# MAIN_Schematic.net
KiCad netlist of a schematic drawn in Altium Designer
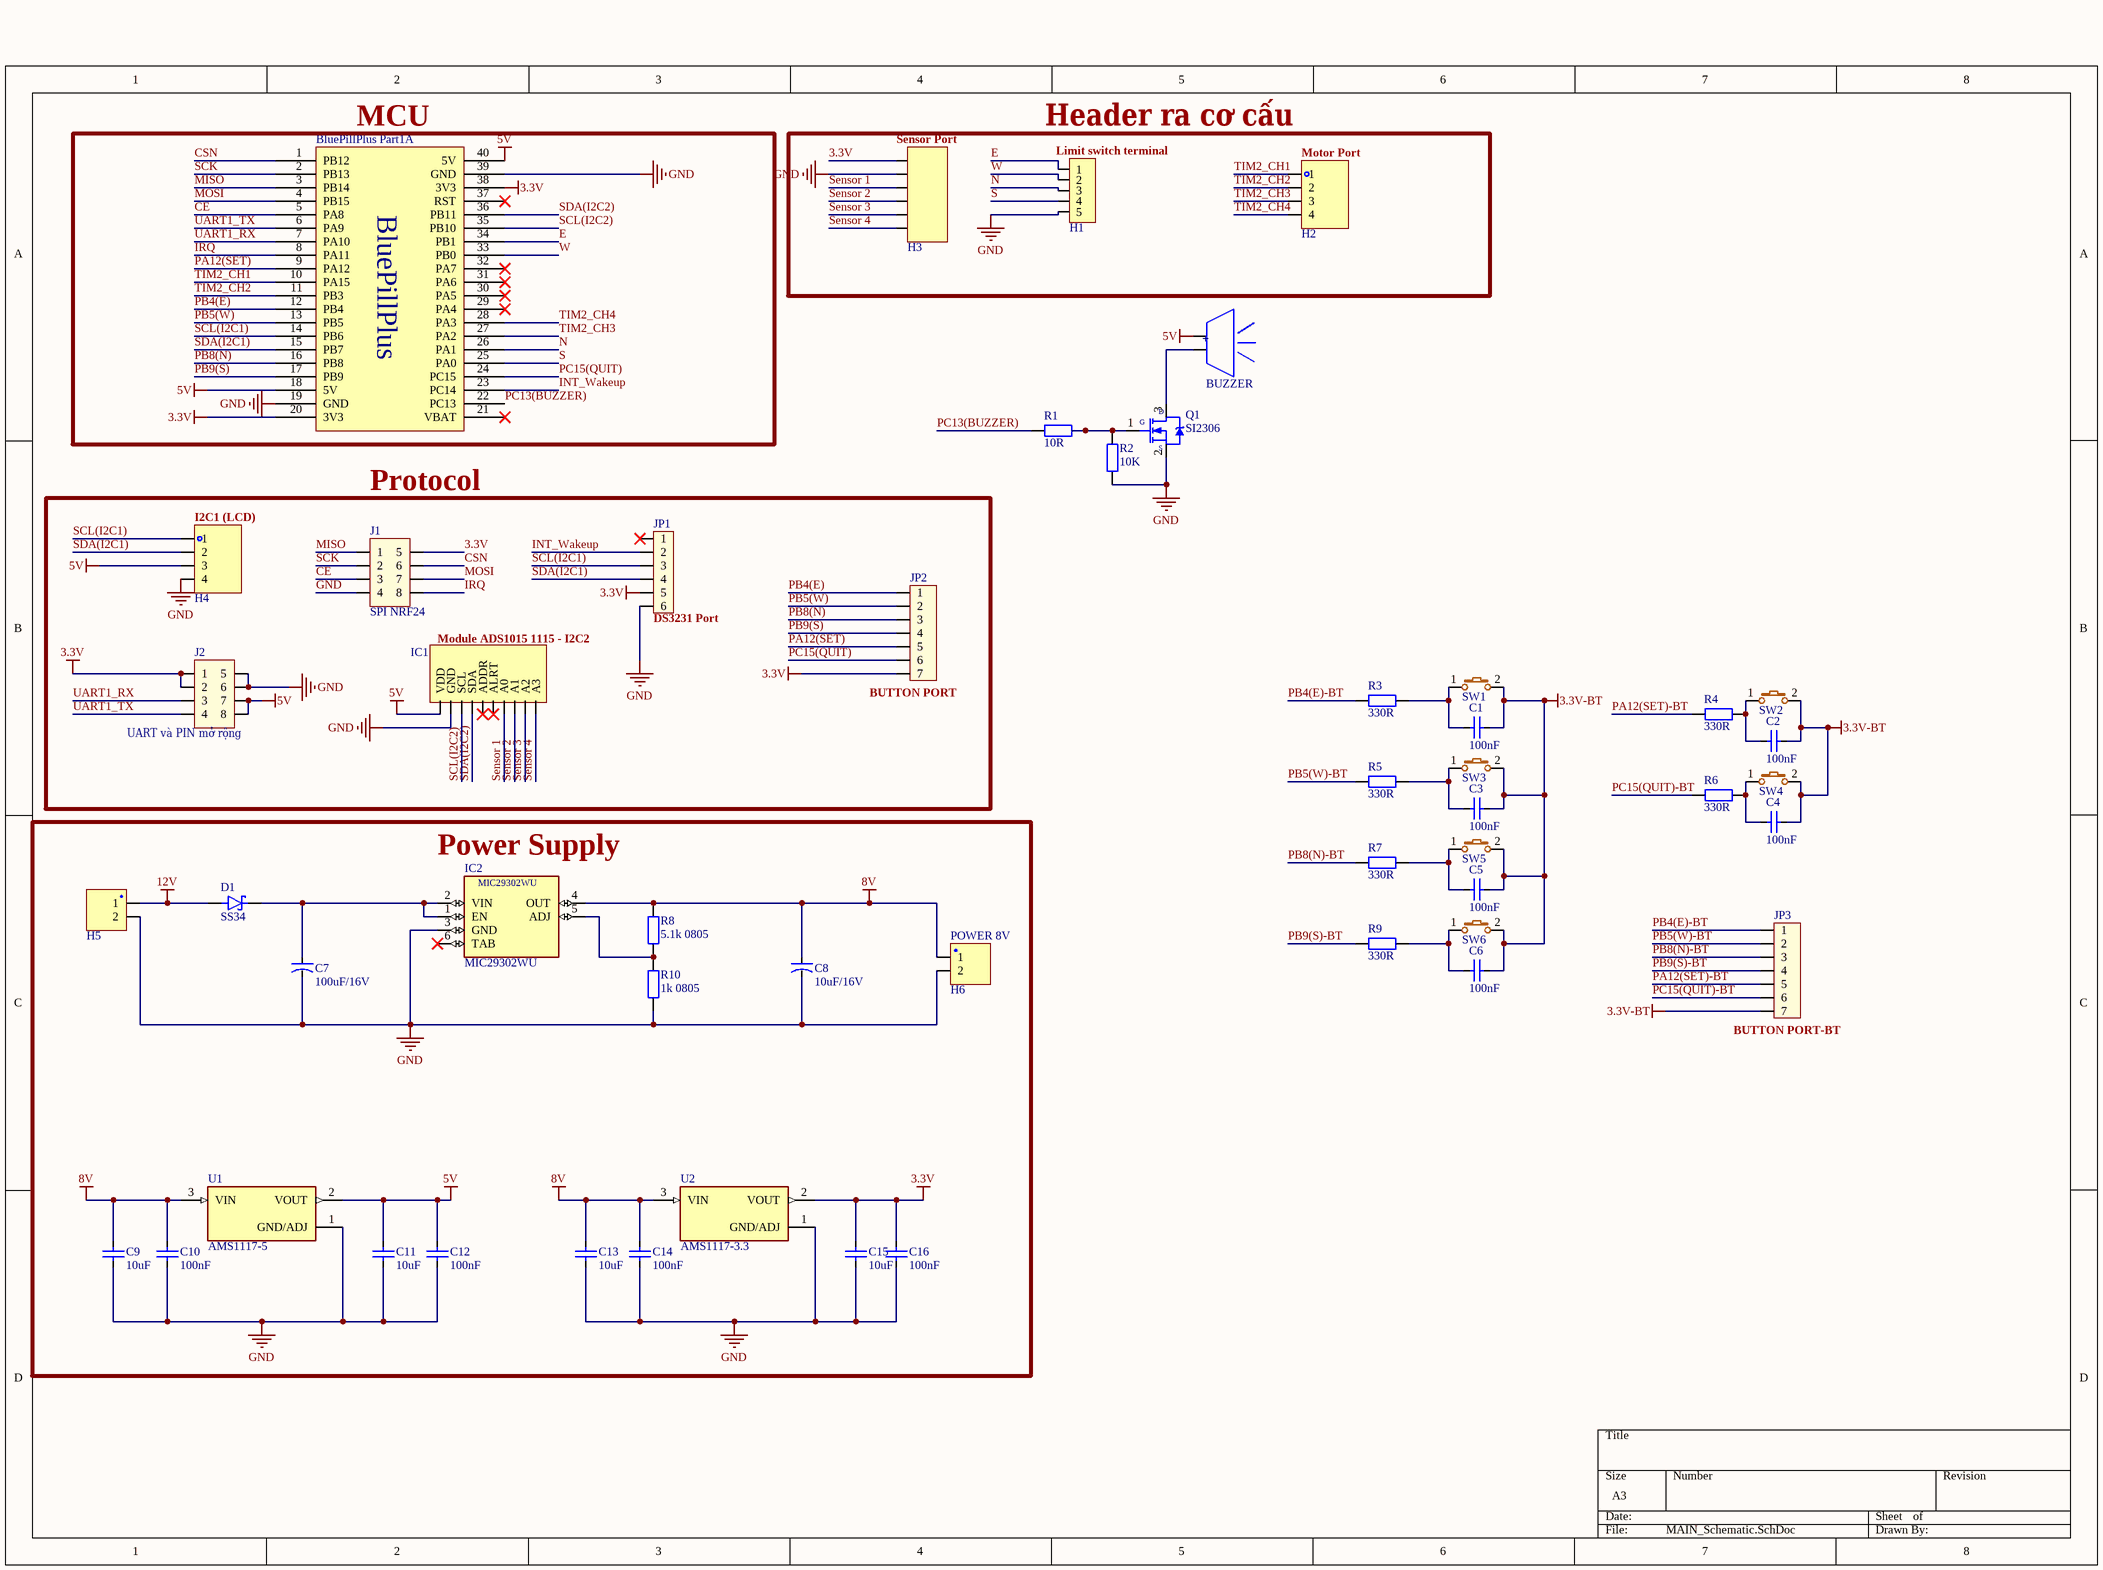
[diagram p0: MAIN_Schematic.SchDoc]

(export (version "E")
  (design (tool "Eeschema 10.0.6"))
  (components
    (comp (ref "BluePillPlus Part1")
      (value "U?")
      (footprint "BluePillPlus")
      (description "BluePillPlus")
      (libsource (lib "BluePillPlus") (part "BluePillPlus"))
    )
    (comp (ref "BUZZER")
      (value "Buzzer")
      (footprint "Buzzer 9mm")
      (description "spk buzz coi loa")
      (libsource (lib "4E_Projects_SCHLib") (part "Buzzer"))
    )
    (comp (ref "C1")
      (value "100nF")
      (footprint "CAP_0805")
      (description "Capacitor")
      (fields (field (name "PUBLISHER") "Altium Limited"))
      (libsource (lib "My Library") (part "CapSMD"))
    )
    (comp (ref "C2")
      (value "100nF")
      (footprint "CAP_0805")
      (description "Capacitor")
      (fields (field (name "PUBLISHER") "Altium Limited"))
      (libsource (lib "My Library") (part "CapSMD"))
    )
    (comp (ref "C3")
      (value "100nF")
      (footprint "CAP_0805")
      (description "Capacitor")
      (fields (field (name "PUBLISHER") "Altium Limited"))
      (libsource (lib "My Library") (part "CapSMD"))
    )
    (comp (ref "C4")
      (value "100nF")
      (footprint "CAP_0805")
      (description "Capacitor")
      (fields (field (name "PUBLISHER") "Altium Limited"))
      (libsource (lib "My Library") (part "CapSMD"))
    )
    (comp (ref "C5")
      (value "100nF")
      (footprint "CAP_0805")
      (description "Capacitor")
      (fields (field (name "PUBLISHER") "Altium Limited"))
      (libsource (lib "My Library") (part "CapSMD"))
    )
    (comp (ref "C6")
      (value "100nF")
      (footprint "CAP_0805")
      (description "Capacitor")
      (fields (field (name "PUBLISHER") "Altium Limited"))
      (libsource (lib "My Library") (part "CapSMD"))
    )
    (comp (ref "C7")
      (value "100uF/16V")
      (footprint "CA-ALU-5")
      (description "Capacitor (Semiconductor SIM Model)")
      (fields (field (name "PUBLISHER") "Altium Limited"))
      (libsource (lib "My Library") (part "CAP-ALU-DIP"))
    )
    (comp (ref "C8")
      (value "10uF/16V")
      (footprint "CA-ALU-5")
      (description "Capacitor (Semiconductor SIM Model)")
      (fields (field (name "PUBLISHER") "Altium Limited"))
      (libsource (lib "My Library") (part "CAP-ALU-DIP"))
    )
    (comp (ref "C9")
      (value "10uF")
      (footprint "CAP_0805")
      (description "Capacitor")
      (fields (field (name "PUBLISHER") "Altium Limited"))
      (libsource (lib "My Library") (part "CapSMD"))
    )
    (comp (ref "C10")
      (value "100nF")
      (footprint "CAP_0805")
      (description "Capacitor")
      (fields (field (name "PUBLISHER") "Altium Limited"))
      (libsource (lib "My Library") (part "CapSMD"))
    )
    (comp (ref "C11")
      (value "10uF")
      (footprint "CAP_0805")
      (description "Capacitor")
      (fields (field (name "PUBLISHER") "Altium Limited"))
      (libsource (lib "My Library") (part "CapSMD"))
    )
    (comp (ref "C12")
      (value "100nF")
      (footprint "CAP_0805")
      (description "Capacitor")
      (fields (field (name "PUBLISHER") "Altium Limited"))
      (libsource (lib "My Library") (part "CapSMD"))
    )
    (comp (ref "C13")
      (value "10uF")
      (footprint "CAP_0805")
      (description "Capacitor")
      (fields (field (name "PUBLISHER") "Altium Limited"))
      (libsource (lib "My Library") (part "CapSMD"))
    )
    (comp (ref "C14")
      (value "100nF")
      (footprint "CAP_0805")
      (description "Capacitor")
      (fields (field (name "PUBLISHER") "Altium Limited"))
      (libsource (lib "My Library") (part "CapSMD"))
    )
    (comp (ref "C15")
      (value "10uF")
      (footprint "CAP_0805")
      (description "Capacitor")
      (fields (field (name "PUBLISHER") "Altium Limited"))
      (libsource (lib "My Library") (part "CapSMD"))
    )
    (comp (ref "C16")
      (value "100nF")
      (footprint "CAP_0805")
      (description "Capacitor")
      (fields (field (name "PUBLISHER") "Altium Limited"))
      (libsource (lib "My Library") (part "CapSMD"))
    )
    (comp (ref "D1")
      (value "SS34")
      (footprint "DIOM4325X244N")
      (description "4A, 40V, Schottky Rectifier")
      (fields (field (name "MF") "Taiwan Semiconductor") (field (name "MP") "SSB44"))
      (libsource (lib "SSB44") (part "SSB44"))
    )
    (comp (ref "H1")
      (value "Limit switch terminal")
      (footprint "Header 5P 5.08")
      (libsource (lib "4E_Projects_SCHLib") (part "Header 5P"))
    )
    (comp (ref "H2")
      (value "Motor Port")
      (footprint "Header 4P 5.08")
      (libsource (lib "4E_Projects_SCHLib") (part "Header 4P"))
    )
    (comp (ref "H3")
      (value "Sensor Port")
      (footprint "Header 6P 5.08")
      (libsource (lib "4E_Projects_SCHLib") (part "Header 6P"))
    )
    (comp (ref "H4")
      (value "I2C1 (LCD)")
      (footprint "XH2.54 4P")
      (libsource (lib "4E_Projects_SCHLib") (part "Header 4P"))
    )
    (comp (ref "H5") (value "Header 2P") (footprint "KF128-5.0-2P") (libsource (lib "") (part "Header 2P_1")))
    (comp (ref "H6")
      (value "POWER 8V")
      (footprint "KF128-5.0-2P")
      (libsource (lib "4E_Projects_SCHLib") (part "Header 2P"))
    )
    (comp (ref "IC1")
      (value "Module ADS1015 1115 - I2C2")
      (footprint "ADS1015 1115")
      (description "Module ADS1015 1115 ADC 12Bit 16Bit")
      (libsource (lib "4E_Projects_SCHLib") (part "Module ADS1015 1115"))
    )
    (comp (ref "IC2")
      (value "MIC29302WU")
      (footprint "TO263-5")
      (description "Linear Voltage Regulator IC 1 Output 3A TO-263-5")
      (fields (field (name "MF") "Microchip Technology"))
      (libsource (lib "MIC29302WU") (part "MIC29302WU"))
    )
    (comp (ref "J1")
      (value "SPI NRF24")
      (footprint "JP4-C2T")
      (description "Connector 4x2")
      (libsource (lib "My Library") (part "JP4x2"))
    )
    (comp (ref "J2")
      (value "UART và PIN mở rộng")
      (footprint "JP4x2")
      (description "Connector 4x2")
      (libsource (lib "My Library") (part "JP4x2"))
    )
    (comp (ref "JP1")
      (value "DS3231 Port")
      (footprint "JP6-C1T")
      (description "JP6 PIN")
      (libsource (lib "My Library") (part "JP6"))
    )
    (comp (ref "JP2")
      (value "BUTTON PORT")
      (footprint "Header7")
      (description "Connector 7")
      (libsource (lib "My Library") (part "Header7"))
    )
    (comp (ref "JP3")
      (value "BUTTON PORT-BT")
      (footprint "Header7")
      (description "Connector 7")
      (libsource (lib "My Library") (part "Header7"))
    )
    (comp (ref "Q1")
      (value "SI2306")
      (footprint "SOT23")
      (description "SI2306 N-Mosfet 3.5A 30V SOT-23")
      (libsource (lib "My Library") (part "SI2304"))
    )
    (comp (ref "R1")
      (value "10R")
      (footprint "RES-SMD-0805")
      (description "Resistor SMD")
      (fields
        (field (name "MANUFACTURER") "Generic Components")
        (field (name "PUBLISHER") "Altium Hobart Technology Centre")
      )
      (libsource (lib "My Library") (part "Resistor - SMD"))
    )
    (comp (ref "R2")
      (value "10K")
      (footprint "RES-SMD-0805")
      (description "Resistor SMD")
      (fields
        (field (name "MANUFACTURER") "Generic Components")
        (field (name "PUBLISHER") "Altium Hobart Technology Centre")
      )
      (libsource (lib "My Library") (part "Resistor - SMD"))
    )
    (comp (ref "R3")
      (value "330R")
      (footprint "RES-SMD-0805")
      (description "Resistor SMD")
      (fields
        (field (name "MANUFACTURER") "Generic Components")
        (field (name "PUBLISHER") "Altium Hobart Technology Centre")
      )
      (libsource (lib "My Library") (part "Resistor - SMD"))
    )
    (comp (ref "R4")
      (value "330R")
      (footprint "RES-SMD-0805")
      (description "Resistor SMD")
      (fields
        (field (name "MANUFACTURER") "Generic Components")
        (field (name "PUBLISHER") "Altium Hobart Technology Centre")
      )
      (libsource (lib "My Library") (part "Resistor - SMD"))
    )
    (comp (ref "R5")
      (value "330R")
      (footprint "RES-SMD-0805")
      (description "Resistor SMD")
      (fields
        (field (name "MANUFACTURER") "Generic Components")
        (field (name "PUBLISHER") "Altium Hobart Technology Centre")
      )
      (libsource (lib "My Library") (part "Resistor - SMD"))
    )
    (comp (ref "R6")
      (value "330R")
      (footprint "RES-SMD-0805")
      (description "Resistor SMD")
      (fields
        (field (name "MANUFACTURER") "Generic Components")
        (field (name "PUBLISHER") "Altium Hobart Technology Centre")
      )
      (libsource (lib "My Library") (part "Resistor - SMD"))
    )
    (comp (ref "R7")
      (value "330R")
      (footprint "RES-SMD-0805")
      (description "Resistor SMD")
      (fields
        (field (name "MANUFACTURER") "Generic Components")
        (field (name "PUBLISHER") "Altium Hobart Technology Centre")
      )
      (libsource (lib "My Library") (part "Resistor - SMD"))
    )
    (comp (ref "R8")
      (value "5.1k 0805")
      (footprint "RES-SMD-0805")
      (description "Resistor SMD")
      (fields
        (field (name "MANUFACTURER") "Generic Components")
        (field (name "PUBLISHER") "Altium Hobart Technology Centre")
      )
      (libsource (lib "My Library") (part "Resistor - SMD"))
    )
    (comp (ref "R9")
      (value "330R")
      (footprint "RES-SMD-0805")
      (description "Resistor SMD")
      (fields
        (field (name "MANUFACTURER") "Generic Components")
        (field (name "PUBLISHER") "Altium Hobart Technology Centre")
      )
      (libsource (lib "My Library") (part "Resistor - SMD"))
    )
    (comp (ref "R10")
      (value "1k 0805")
      (footprint "RES-SMD-0805")
      (description "Resistor SMD")
      (fields
        (field (name "MANUFACTURER") "Generic Components")
        (field (name "PUBLISHER") "Altium Hobart Technology Centre")
      )
      (libsource (lib "My Library") (part "Resistor - SMD"))
    )
    (comp (ref "SW1")
      (value "Nut nhan 7mm")
      (footprint "BUTTON 4 PIN")
      (libsource (lib "4E_Projects_SCHLib") (part "Button"))
    )
    (comp (ref "SW2")
      (value "Nut nhan 7mm")
      (footprint "BUTTON 4 PIN")
      (libsource (lib "4E_Projects_SCHLib") (part "Button"))
    )
    (comp (ref "SW3")
      (value "Nut nhan 7mm")
      (footprint "BUTTON 4 PIN")
      (libsource (lib "4E_Projects_SCHLib") (part "Button"))
    )
    (comp (ref "SW4")
      (value "Nut nhan 7mm")
      (footprint "BUTTON 4 PIN")
      (libsource (lib "4E_Projects_SCHLib") (part "Button"))
    )
    (comp (ref "SW5")
      (value "Nut nhan 7mm")
      (footprint "BUTTON 4 PIN")
      (libsource (lib "4E_Projects_SCHLib") (part "Button"))
    )
    (comp (ref "SW6")
      (value "Nut nhan 7mm")
      (footprint "BUTTON 4 PIN")
      (libsource (lib "4E_Projects_SCHLib") (part "Button"))
    )
    (comp (ref "U1")
      (value "AMS1117-5")
      (footprint "SOT229P700X180-4N")
      (description "1A LOW DROPOUT VOLTAGE REGULATOR")
      (fields (field (name "MP") "AMS1117-5.0") (field (name "MF") "ams"))
      (libsource (lib "AMS1117-5.0") (part "AMS1117-5.0"))
    )
    (comp (ref "U2")
      (value "AMS1117-3.3")
      (footprint "SOT229P700X180-4N")
      (description "1A LOW DROPOUT VOLTAGE REGULATOR")
      (fields (field (name "MP") "AMS1117-5.0") (field (name "MF") "ams"))
      (libsource (lib "AMS1117-5.0") (part "AMS1117-5.0"))
    )
  )
  (nets
    (net (code "2") (name "/CE") (class "Default")
      (node (ref "BluePillPlus Part1") (pin "5") (pinfunction "PA8_5") (pintype "passive"))
      (node (ref "J1") (pin "3") (pinfunction "3_3") (pintype "passive"))
    )
    (net (code "3") (name "/CSN") (class "Default")
      (node (ref "BluePillPlus Part1") (pin "1") (pinfunction "PB12_1") (pintype "passive"))
      (node (ref "J1") (pin "6") (pinfunction "6_6") (pintype "passive"))
    )
    (net (code "4") (name "/E") (class "Default")
      (node (ref "BluePillPlus Part1") (pin "34") (pinfunction "PB1_34") (pintype "passive"))
      (node (ref "H1") (pin "1") (pinfunction "1_1") (pintype "passive"))
    )
    (net (code "5") (name "/INT_Wakeup") (class "Default")
      (node (ref "BluePillPlus Part1") (pin "23") (pinfunction "PC14_23") (pintype "passive"))
      (node (ref "JP1") (pin "2") (pinfunction "2_2") (pintype "passive"))
    )
    (net (code "6") (name "/IRQ") (class "Default")
      (node (ref "BluePillPlus Part1") (pin "8") (pinfunction "PA11_8") (pintype "passive"))
      (node (ref "J1") (pin "8") (pinfunction "8_8") (pintype "passive"))
    )
    (net (code "7") (name "/MISO") (class "Default")
      (node (ref "BluePillPlus Part1") (pin "3") (pinfunction "PB14_3") (pintype "passive"))
      (node (ref "J1") (pin "1") (pinfunction "1_1") (pintype "passive"))
    )
    (net (code "8") (name "/MOSI") (class "Default")
      (node (ref "BluePillPlus Part1") (pin "4") (pinfunction "PB15_4") (pintype "passive"))
      (node (ref "J1") (pin "7") (pinfunction "7_7") (pintype "passive"))
    )
    (net (code "9") (name "/N") (class "Default")
      (node (ref "BluePillPlus Part1") (pin "26") (pinfunction "PA1_26") (pintype "passive"))
      (node (ref "H1") (pin "3") (pinfunction "3_3") (pintype "passive"))
    )
    (net (code "10") (name "/PA12(SET)") (class "Default")
      (node (ref "BluePillPlus Part1") (pin "9") (pinfunction "PA12_9") (pintype "passive"))
      (node (ref "JP2") (pin "5") (pinfunction "5_5") (pintype "passive"))
    )
    (net (code "11") (name "/PA12(SET)-BT") (class "Default")
      (node (ref "JP3") (pin "5") (pinfunction "5_5") (pintype "passive"))
      (node (ref "R4") (pin "2") (pinfunction "2_2") (pintype "passive"))
    )
    (net (code "12") (name "/PB4(E)") (class "Default")
      (node (ref "BluePillPlus Part1") (pin "12") (pinfunction "PB4_12") (pintype "passive"))
      (node (ref "JP2") (pin "1") (pinfunction "1_1") (pintype "passive"))
    )
    (net (code "13") (name "/PB4(E)-BT") (class "Default")
      (node (ref "JP3") (pin "1") (pinfunction "1_1") (pintype "passive"))
      (node (ref "R3") (pin "2") (pinfunction "2_2") (pintype "passive"))
    )
    (net (code "14") (name "/PB5(W)") (class "Default")
      (node (ref "BluePillPlus Part1") (pin "13") (pinfunction "PB5_13") (pintype "passive"))
      (node (ref "JP2") (pin "2") (pinfunction "2_2") (pintype "passive"))
    )
    (net (code "15") (name "/PB5(W)-BT") (class "Default")
      (node (ref "JP3") (pin "2") (pinfunction "2_2") (pintype "passive"))
      (node (ref "R5") (pin "2") (pinfunction "2_2") (pintype "passive"))
    )
    (net (code "16") (name "/PB8(N)") (class "Default")
      (node (ref "BluePillPlus Part1") (pin "16") (pinfunction "PB8_16") (pintype "passive"))
      (node (ref "JP2") (pin "3") (pinfunction "3_3") (pintype "passive"))
    )
    (net (code "17") (name "/PB8(N)-BT") (class "Default")
      (node (ref "JP3") (pin "3") (pinfunction "3_3") (pintype "passive"))
      (node (ref "R7") (pin "2") (pinfunction "2_2") (pintype "passive"))
    )
    (net (code "18") (name "/PB9(S)") (class "Default")
      (node (ref "BluePillPlus Part1") (pin "17") (pinfunction "PB9_17") (pintype "passive"))
      (node (ref "JP2") (pin "4") (pinfunction "4_4") (pintype "passive"))
    )
    (net (code "19") (name "/PB9(S)-BT") (class "Default")
      (node (ref "JP3") (pin "4") (pinfunction "4_4") (pintype "passive"))
      (node (ref "R9") (pin "2") (pinfunction "2_2") (pintype "passive"))
    )
    (net (code "20") (name "/PC13(BUZZER)") (class "Default")
      (node (ref "BluePillPlus Part1") (pin "22") (pinfunction "PC13_22") (pintype "passive"))
      (node (ref "R1") (pin "1") (pinfunction "1_1") (pintype "passive"))
    )
    (net (code "21") (name "/PC15(QUIT)") (class "Default")
      (node (ref "BluePillPlus Part1") (pin "24") (pinfunction "PC15_24") (pintype "passive"))
      (node (ref "JP2") (pin "6") (pinfunction "6_6") (pintype "passive"))
    )
    (net (code "22") (name "/PC15(QUIT)-BT") (class "Default")
      (node (ref "JP3") (pin "6") (pinfunction "6_6") (pintype "passive"))
      (node (ref "R6") (pin "2") (pinfunction "2_2") (pintype "passive"))
    )
    (net (code "23") (name "/S") (class "Default")
      (node (ref "BluePillPlus Part1") (pin "25") (pinfunction "PA0_25") (pintype "passive"))
      (node (ref "H1") (pin "4") (pinfunction "4_4") (pintype "passive"))
    )
    (net (code "24") (name "/SCK") (class "Default")
      (node (ref "BluePillPlus Part1") (pin "2") (pinfunction "PB13_2") (pintype "passive"))
      (node (ref "J1") (pin "2") (pinfunction "2_2") (pintype "passive"))
    )
    (net (code "25") (name "/SCL(I2C1)") (class "Default")
      (node (ref "BluePillPlus Part1") (pin "14") (pinfunction "PB6_14") (pintype "passive"))
      (node (ref "H4") (pin "1") (pinfunction "1_1") (pintype "passive"))
      (node (ref "JP1") (pin "3") (pinfunction "3_3") (pintype "passive"))
    )
    (net (code "26") (name "/SCL(I2C2)") (class "Default")
      (node (ref "BluePillPlus Part1") (pin "35") (pinfunction "PB10_35") (pintype "passive"))
      (node (ref "IC1") (pin "3") (pinfunction "SCL_3") (pintype "passive"))
    )
    (net (code "27") (name "/SDA(I2C1)") (class "Default")
      (node (ref "BluePillPlus Part1") (pin "15") (pinfunction "PB7_15") (pintype "passive"))
      (node (ref "H4") (pin "2") (pinfunction "2_2") (pintype "passive"))
      (node (ref "JP1") (pin "4") (pinfunction "4_4") (pintype "passive"))
    )
    (net (code "28") (name "/SDA(I2C2)") (class "Default")
      (node (ref "BluePillPlus Part1") (pin "36") (pinfunction "PB11_36") (pintype "passive"))
      (node (ref "IC1") (pin "4") (pinfunction "SDA_4") (pintype "passive"))
    )
    (net (code "29") (name "/Sensor 1") (class "Default")
      (node (ref "H3") (pin "3") (pinfunction "3_3") (pintype "passive"))
      (node (ref "IC1") (pin "7") (pinfunction "A0_7") (pintype "passive"))
    )
    (net (code "30") (name "/Sensor 2") (class "Default")
      (node (ref "H3") (pin "4") (pinfunction "4_4") (pintype "passive"))
      (node (ref "IC1") (pin "8") (pinfunction "A1_8") (pintype "passive"))
    )
    (net (code "31") (name "/Sensor 3") (class "Default")
      (node (ref "H3") (pin "5") (pinfunction "5_5") (pintype "passive"))
      (node (ref "IC1") (pin "9") (pinfunction "A2_9") (pintype "passive"))
    )
    (net (code "32") (name "/Sensor 4") (class "Default")
      (node (ref "H3") (pin "6") (pinfunction "6_6") (pintype "passive"))
      (node (ref "IC1") (pin "10") (pinfunction "A3_10") (pintype "passive"))
    )
    (net (code "33") (name "/TIM2_CH1") (class "Default")
      (node (ref "BluePillPlus Part1") (pin "10") (pinfunction "PA15_10") (pintype "passive"))
      (node (ref "H2") (pin "1") (pinfunction "1_1") (pintype "passive"))
    )
    (net (code "34") (name "/TIM2_CH2") (class "Default")
      (node (ref "BluePillPlus Part1") (pin "11") (pinfunction "PB3_11") (pintype "passive"))
      (node (ref "H2") (pin "2") (pinfunction "2_2") (pintype "passive"))
    )
    (net (code "35") (name "/TIM2_CH3") (class "Default")
      (node (ref "BluePillPlus Part1") (pin "27") (pinfunction "PA2_27") (pintype "passive"))
      (node (ref "H2") (pin "3") (pinfunction "3_3") (pintype "passive"))
    )
    (net (code "36") (name "/TIM2_CH4") (class "Default")
      (node (ref "BluePillPlus Part1") (pin "28") (pinfunction "PA3_28") (pintype "passive"))
      (node (ref "H2") (pin "4") (pinfunction "4_4") (pintype "passive"))
    )
    (net (code "37") (name "/UART1_RX") (class "Default")
      (node (ref "BluePillPlus Part1") (pin "7") (pinfunction "PA10_7") (pintype "passive"))
      (node (ref "J2") (pin "3") (pinfunction "3_3") (pintype "passive"))
    )
    (net (code "38") (name "/UART1_TX") (class "Default")
      (node (ref "BluePillPlus Part1") (pin "6") (pinfunction "PA9_6") (pintype "passive"))
      (node (ref "J2") (pin "4") (pinfunction "4_4") (pintype "passive"))
    )
    (net (code "39") (name "/W") (class "Default")
      (node (ref "BluePillPlus Part1") (pin "33") (pinfunction "PB0_33") (pintype "passive"))
      (node (ref "H1") (pin "2") (pinfunction "2_2") (pintype "passive"))
    )
    (net (code "40") (name "3.3V") (class "Default")
      (node (ref "BluePillPlus Part1") (pin "20") (pinfunction "3V3_20") (pintype "passive"))
      (node (ref "BluePillPlus Part1") (pin "38") (pinfunction "3V3_38") (pintype "passive"))
      (node (ref "C15") (pin "2") (pinfunction "2_2") (pintype "passive"))
      (node (ref "C16") (pin "2") (pinfunction "2_2") (pintype "passive"))
      (node (ref "H3") (pin "1") (pinfunction "1_1") (pintype "passive"))
      (node (ref "J1") (pin "5") (pinfunction "5_5") (pintype "passive"))
      (node (ref "J2") (pin "1") (pinfunction "1_1") (pintype "passive"))
      (node (ref "J2") (pin "2") (pinfunction "2_2") (pintype "passive"))
      (node (ref "JP1") (pin "5") (pinfunction "5_5") (pintype "passive"))
      (node (ref "JP2") (pin "7") (pinfunction "7_7") (pintype "passive"))
      (node (ref "U2") (pin "2") (pinfunction "VOUT_2") (pintype "output"))
    )
    (net (code "41") (name "3.3V-BT") (class "Default")
      (node (ref "C1") (pin "2") (pinfunction "2_2") (pintype "passive"))
      (node (ref "C2") (pin "2") (pinfunction "2_2") (pintype "passive"))
      (node (ref "C3") (pin "2") (pinfunction "2_2") (pintype "passive"))
      (node (ref "C4") (pin "2") (pinfunction "2_2") (pintype "passive"))
      (node (ref "C5") (pin "2") (pinfunction "2_2") (pintype "passive"))
      (node (ref "C6") (pin "2") (pinfunction "2_2") (pintype "passive"))
      (node (ref "JP3") (pin "7") (pinfunction "7_7") (pintype "passive"))
      (node (ref "SW1") (pin "2") (pinfunction "2_2") (pintype "passive"))
      (node (ref "SW2") (pin "2") (pinfunction "2_2") (pintype "passive"))
      (node (ref "SW3") (pin "2") (pinfunction "2_2") (pintype "passive"))
      (node (ref "SW4") (pin "2") (pinfunction "2_2") (pintype "passive"))
      (node (ref "SW5") (pin "2") (pinfunction "2_2") (pintype "passive"))
      (node (ref "SW6") (pin "2") (pinfunction "2_2") (pintype "passive"))
    )
    (net (code "42") (name "5V") (class "Default")
      (node (ref "BUZZER") (pin "1") (pinfunction "1_1") (pintype "passive"))
      (node (ref "BluePillPlus Part1") (pin "18") (pinfunction "5V_18") (pintype "passive"))
      (node (ref "BluePillPlus Part1") (pin "40") (pinfunction "5V_40") (pintype "passive"))
      (node (ref "C11") (pin "2") (pinfunction "2_2") (pintype "passive"))
      (node (ref "C12") (pin "2") (pinfunction "2_2") (pintype "passive"))
      (node (ref "H4") (pin "3") (pinfunction "3_3") (pintype "passive"))
      (node (ref "IC1") (pin "1") (pinfunction "VDD_1") (pintype "passive"))
      (node (ref "J2") (pin "7") (pinfunction "7_7") (pintype "passive"))
      (node (ref "J2") (pin "8") (pinfunction "8_8") (pintype "passive"))
      (node (ref "U1") (pin "2") (pinfunction "VOUT_2") (pintype "output"))
    )
    (net (code "43") (name "8V") (class "Default")
      (node (ref "C10") (pin "2") (pinfunction "2_2") (pintype "passive"))
      (node (ref "C13") (pin "2") (pinfunction "2_2") (pintype "passive"))
      (node (ref "C14") (pin "2") (pinfunction "2_2") (pintype "passive"))
      (node (ref "C8") (pin "1") (pinfunction "1_1") (pintype "passive"))
      (node (ref "C9") (pin "2") (pinfunction "2_2") (pintype "passive"))
      (node (ref "H6") (pin "1") (pinfunction "1_1") (pintype "passive"))
      (node (ref "IC2") (pin "4") (pinfunction "OUT_4") (pintype "bidirectional"))
      (node (ref "R8") (pin "1") (pinfunction "1_1") (pintype "passive"))
      (node (ref "U1") (pin "3") (pinfunction "VIN_3") (pintype "input"))
      (node (ref "U2") (pin "3") (pinfunction "VIN_3") (pintype "input"))
    )
    (net (code "44") (name "12V") (class "Default")
      (node (ref "D1") (pin "A") (pinfunction "A_A") (pintype "passive"))
      (node (ref "H5") (pin "1") (pinfunction "1_1") (pintype "passive"))
    )
    (net (code "45") (name "GND") (class "Default")
      (node (ref "BluePillPlus Part1") (pin "19") (pinfunction "GND_19") (pintype "passive"))
      (node (ref "BluePillPlus Part1") (pin "39") (pinfunction "GND_39") (pintype "passive"))
      (node (ref "C10") (pin "1") (pinfunction "1_1") (pintype "passive"))
      (node (ref "C11") (pin "1") (pinfunction "1_1") (pintype "passive"))
      (node (ref "C12") (pin "1") (pinfunction "1_1") (pintype "passive"))
      (node (ref "C13") (pin "1") (pinfunction "1_1") (pintype "passive"))
      (node (ref "C14") (pin "1") (pinfunction "1_1") (pintype "passive"))
      (node (ref "C15") (pin "1") (pinfunction "1_1") (pintype "passive"))
      (node (ref "C16") (pin "1") (pinfunction "1_1") (pintype "passive"))
      (node (ref "C7") (pin "2") (pinfunction "2_2") (pintype "passive"))
      (node (ref "C8") (pin "2") (pinfunction "2_2") (pintype "passive"))
      (node (ref "C9") (pin "1") (pinfunction "1_1") (pintype "passive"))
      (node (ref "H1") (pin "5") (pinfunction "5_5") (pintype "passive"))
      (node (ref "H3") (pin "2") (pinfunction "2_2") (pintype "passive"))
      (node (ref "H4") (pin "4") (pinfunction "4_4") (pintype "passive"))
      (node (ref "H5") (pin "2") (pinfunction "2_2") (pintype "passive"))
      (node (ref "H6") (pin "2") (pinfunction "2_2") (pintype "passive"))
      (node (ref "IC1") (pin "2") (pinfunction "GND_2") (pintype "passive"))
      (node (ref "IC2") (pin "3") (pinfunction "GND_3") (pintype "bidirectional"))
      (node (ref "J1") (pin "4") (pinfunction "4_4") (pintype "passive"))
      (node (ref "J2") (pin "5") (pinfunction "5_5") (pintype "passive"))
      (node (ref "J2") (pin "6") (pinfunction "6_6") (pintype "passive"))
      (node (ref "JP1") (pin "6") (pinfunction "6_6") (pintype "passive"))
      (node (ref "Q1") (pin "2") (pinfunction "S_2") (pintype "passive"))
      (node (ref "R10") (pin "2") (pinfunction "2_2") (pintype "passive"))
      (node (ref "R2") (pin "2") (pinfunction "2_2") (pintype "passive"))
      (node (ref "U1") (pin "1") (pinfunction "GND/ADJ_1") (pintype "power_in"))
      (node (ref "U2") (pin "1") (pinfunction "GND/ADJ_1") (pintype "power_in"))
    )
    (net (code "46") (name "Net-(C1-Pad1)") (class "Default")
      (node (ref "C1") (pin "1") (pinfunction "1_1") (pintype "passive"))
      (node (ref "R3") (pin "1") (pinfunction "1_1") (pintype "passive"))
      (node (ref "SW1") (pin "1") (pinfunction "1_1") (pintype "passive"))
    )
    (net (code "47") (name "Net-(C2-Pad1)") (class "Default")
      (node (ref "C2") (pin "1") (pinfunction "1_1") (pintype "passive"))
      (node (ref "R4") (pin "1") (pinfunction "1_1") (pintype "passive"))
      (node (ref "SW2") (pin "1") (pinfunction "1_1") (pintype "passive"))
    )
    (net (code "48") (name "Net-(C3-Pad1)") (class "Default")
      (node (ref "C3") (pin "1") (pinfunction "1_1") (pintype "passive"))
      (node (ref "R5") (pin "1") (pinfunction "1_1") (pintype "passive"))
      (node (ref "SW3") (pin "1") (pinfunction "1_1") (pintype "passive"))
    )
    (net (code "49") (name "Net-(C4-Pad1)") (class "Default")
      (node (ref "C4") (pin "1") (pinfunction "1_1") (pintype "passive"))
      (node (ref "R6") (pin "1") (pinfunction "1_1") (pintype "passive"))
      (node (ref "SW4") (pin "1") (pinfunction "1_1") (pintype "passive"))
    )
    (net (code "50") (name "Net-(C5-Pad1)") (class "Default")
      (node (ref "C5") (pin "1") (pinfunction "1_1") (pintype "passive"))
      (node (ref "R7") (pin "1") (pinfunction "1_1") (pintype "passive"))
      (node (ref "SW5") (pin "1") (pinfunction "1_1") (pintype "passive"))
    )
    (net (code "51") (name "Net-(C6-Pad1)") (class "Default")
      (node (ref "C6") (pin "1") (pinfunction "1_1") (pintype "passive"))
      (node (ref "R9") (pin "1") (pinfunction "1_1") (pintype "passive"))
      (node (ref "SW6") (pin "1") (pinfunction "1_1") (pintype "passive"))
    )
    (net (code "52") (name "Net-(D1-K)") (class "Default")
      (node (ref "C7") (pin "1") (pinfunction "1_1") (pintype "passive"))
      (node (ref "D1") (pin "C") (pinfunction "K_C") (pintype "passive"))
      (node (ref "IC2") (pin "1") (pinfunction "EN_1") (pintype "bidirectional"))
      (node (ref "IC2") (pin "2") (pinfunction "VIN_2") (pintype "bidirectional"))
    )
    (net (code "53") (name "Net-(IC2-ADJ)") (class "Default")
      (node (ref "IC2") (pin "5") (pinfunction "ADJ_5") (pintype "bidirectional"))
      (node (ref "R10") (pin "1") (pinfunction "1_1") (pintype "passive"))
      (node (ref "R8") (pin "2") (pinfunction "2_2") (pintype "passive"))
    )
    (net (code "54") (name "Net-(Q1-D)") (class "Default")
      (node (ref "BUZZER") (pin "2") (pinfunction "2_2") (pintype "passive"))
      (node (ref "Q1") (pin "3") (pinfunction "D_3") (pintype "passive"))
    )
    (net (code "55") (name "Net-(Q1-G)") (class "Default")
      (node (ref "Q1") (pin "1") (pinfunction "G_1") (pintype "passive"))
      (node (ref "R1") (pin "2") (pinfunction "2_2") (pintype "passive"))
      (node (ref "R2") (pin "1") (pinfunction "1_1") (pintype "passive"))
    )
    (net (code "56") (name "unconnected-(BluePillPlus Part1A-PA4-Pad29)") (class "Default")
      (node (ref "BluePillPlus Part1") (pin "29") (pinfunction "PA4_29") (pintype "passive+no_connect"))
    )
    (net (code "57") (name "unconnected-(BluePillPlus Part1A-PA5-Pad30)") (class "Default")
      (node (ref "BluePillPlus Part1") (pin "30") (pinfunction "PA5_30") (pintype "passive+no_connect"))
    )
    (net (code "58") (name "unconnected-(BluePillPlus Part1A-PA6-Pad31)") (class "Default")
      (node (ref "BluePillPlus Part1") (pin "31") (pinfunction "PA6_31") (pintype "passive+no_connect"))
    )
    (net (code "59") (name "unconnected-(BluePillPlus Part1A-PA7-Pad32)") (class "Default")
      (node (ref "BluePillPlus Part1") (pin "32") (pinfunction "PA7_32") (pintype "passive+no_connect"))
    )
    (net (code "60") (name "unconnected-(BluePillPlus Part1A-RST-Pad37)") (class "Default")
      (node (ref "BluePillPlus Part1") (pin "37") (pinfunction "RST_37") (pintype "passive+no_connect"))
    )
    (net (code "61") (name "unconnected-(BluePillPlus Part1A-VBAT-Pad21)") (class "Default")
      (node (ref "BluePillPlus Part1") (pin "21") (pinfunction "VBAT_21") (pintype "passive+no_connect"))
    )
    (net (code "62") (name "unconnected-(IC1-ADDR-Pad5)") (class "Default")
      (node (ref "IC1") (pin "5") (pinfunction "ADDR_5") (pintype "passive+no_connect"))
    )
    (net (code "63") (name "unconnected-(IC1-ALRT-Pad6)") (class "Default")
      (node (ref "IC1") (pin "6") (pinfunction "ALRT_6") (pintype "passive+no_connect"))
    )
    (net (code "64") (name "unconnected-(IC2-TAB-Pad6)") (class "Default")
      (node (ref "IC2") (pin "6") (pinfunction "TAB_6") (pintype "bidirectional+no_connect"))
    )
    (net (code "65") (name "unconnected-(JP1-Pad1)") (class "Default")
      (node (ref "JP1") (pin "1") (pinfunction "1_1") (pintype "passive+no_connect"))
    )
  )
)
